# zxuno.net
KiCad netlist of a schematic drawn in EAGLE
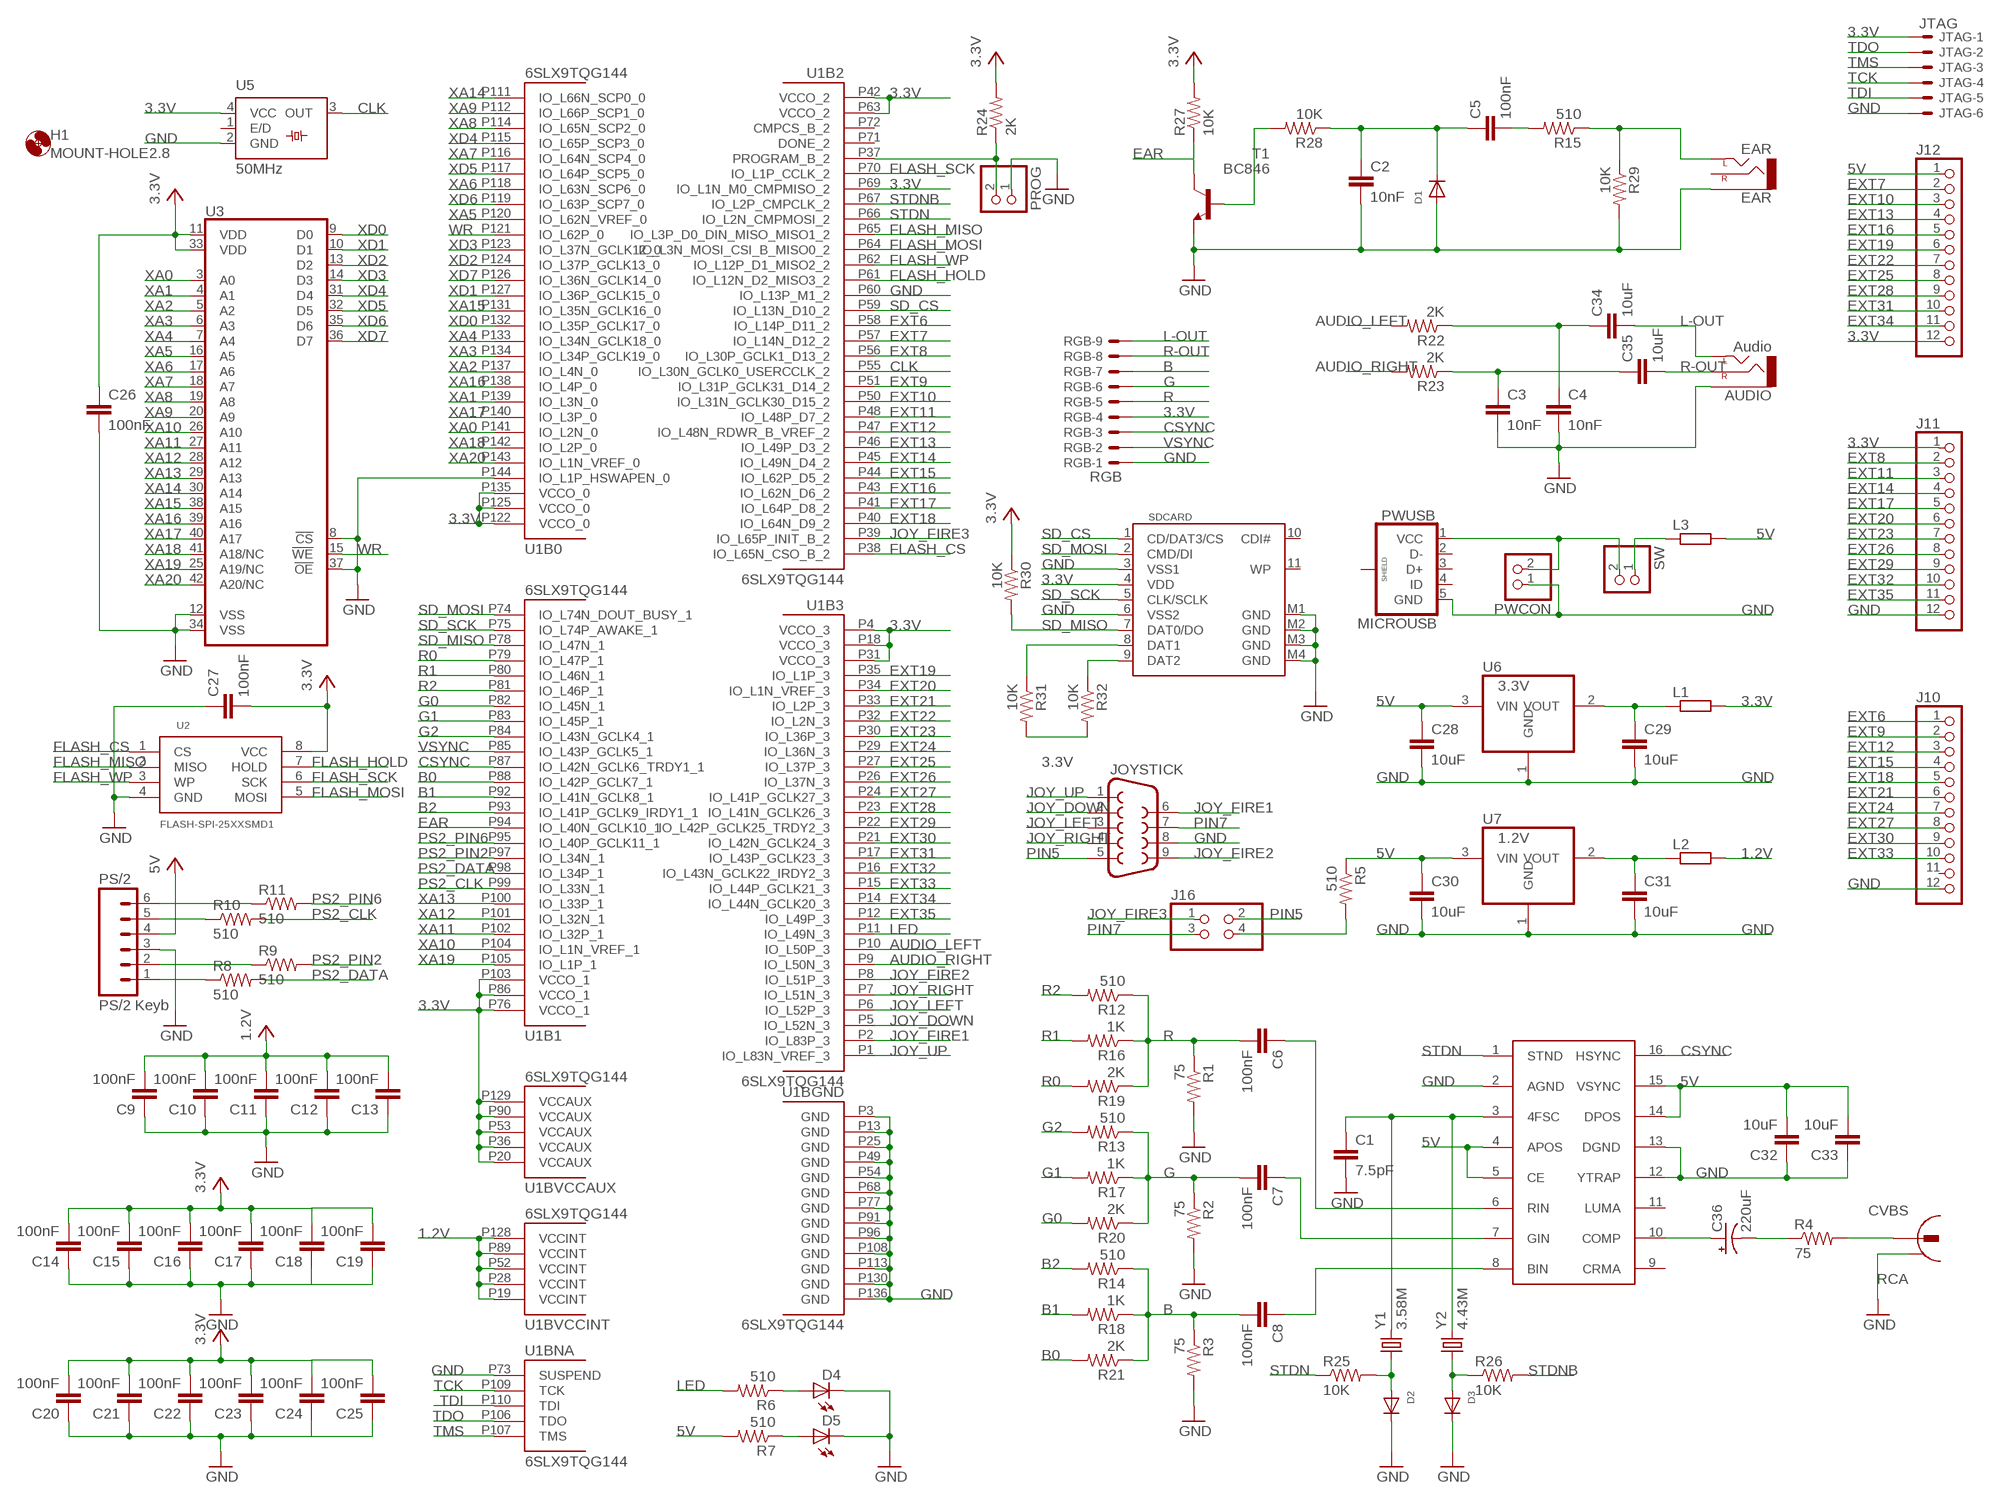
[diagram p0: schematic, sheet 1]

(export (version "E")
  (design (tool "Eeschema 10.0.6"))
  (components
    (comp (ref "AUDIO")
      (value "Audio")
      (footprint "eagle-import:AUDIO-JACK")
      (libsource (lib "eagle-import") (part "AUDIO-JACKPTH"))
    )
    (comp (ref "C1")
      (value "7.5pF")
      (footprint "eagle-import:C0805")
      (libsource (lib "eagle-import") (part "C-EUC0805"))
    )
    (comp (ref "C2")
      (value "10nF")
      (footprint "eagle-import:C0805")
      (libsource (lib "eagle-import") (part "C-EUC0805"))
    )
    (comp (ref "C3")
      (value "10nF")
      (footprint "eagle-import:C0805")
      (libsource (lib "eagle-import") (part "C-EUC0805"))
    )
    (comp (ref "C4")
      (value "10nF")
      (footprint "eagle-import:C0805")
      (libsource (lib "eagle-import") (part "C-EUC0805"))
    )
    (comp (ref "C5")
      (value "100nF")
      (footprint "eagle-import:C0603")
      (libsource (lib "eagle-import") (part "C-EUC0603"))
    )
    (comp (ref "C6")
      (value "100nF")
      (footprint "eagle-import:C0603")
      (libsource (lib "eagle-import") (part "C-EUC0603"))
    )
    (comp (ref "C7")
      (value "100nF")
      (footprint "eagle-import:C0603")
      (libsource (lib "eagle-import") (part "C-EUC0603"))
    )
    (comp (ref "C8")
      (value "100nF")
      (footprint "eagle-import:C0603")
      (libsource (lib "eagle-import") (part "C-EUC0603"))
    )
    (comp (ref "C9")
      (value "100nF")
      (footprint "eagle-import:C0603")
      (libsource (lib "eagle-import") (part "C-EUC0603"))
    )
    (comp (ref "C10")
      (value "100nF")
      (footprint "eagle-import:C0603")
      (libsource (lib "eagle-import") (part "C-EUC0603"))
    )
    (comp (ref "C11")
      (value "100nF")
      (footprint "eagle-import:C0603")
      (libsource (lib "eagle-import") (part "C-EUC0603"))
    )
    (comp (ref "C12")
      (value "100nF")
      (footprint "eagle-import:C0603")
      (libsource (lib "eagle-import") (part "C-EUC0603"))
    )
    (comp (ref "C13")
      (value "100nF")
      (footprint "eagle-import:C0603")
      (libsource (lib "eagle-import") (part "C-EUC0603"))
    )
    (comp (ref "C14")
      (value "100nF")
      (footprint "eagle-import:C0603")
      (libsource (lib "eagle-import") (part "C-EUC0603"))
    )
    (comp (ref "C15")
      (value "100nF")
      (footprint "eagle-import:C0603")
      (libsource (lib "eagle-import") (part "C-EUC0603"))
    )
    (comp (ref "C16")
      (value "100nF")
      (footprint "eagle-import:C0603")
      (libsource (lib "eagle-import") (part "C-EUC0603"))
    )
    (comp (ref "C17")
      (value "100nF")
      (footprint "eagle-import:C0603")
      (libsource (lib "eagle-import") (part "C-EUC0603"))
    )
    (comp (ref "C18")
      (value "100nF")
      (footprint "eagle-import:C0603")
      (libsource (lib "eagle-import") (part "C-EUC0603"))
    )
    (comp (ref "C19")
      (value "100nF")
      (footprint "eagle-import:C0603")
      (libsource (lib "eagle-import") (part "C-EUC0603"))
    )
    (comp (ref "C20")
      (value "100nF")
      (footprint "eagle-import:C0603")
      (libsource (lib "eagle-import") (part "C-EUC0603"))
    )
    (comp (ref "C21")
      (value "100nF")
      (footprint "eagle-import:C0603")
      (libsource (lib "eagle-import") (part "C-EUC0603"))
    )
    (comp (ref "C22")
      (value "100nF")
      (footprint "eagle-import:C0603")
      (libsource (lib "eagle-import") (part "C-EUC0603"))
    )
    (comp (ref "C23")
      (value "100nF")
      (footprint "eagle-import:C0603")
      (libsource (lib "eagle-import") (part "C-EUC0603"))
    )
    (comp (ref "C24")
      (value "100nF")
      (footprint "eagle-import:C0603")
      (libsource (lib "eagle-import") (part "C-EUC0603"))
    )
    (comp (ref "C25")
      (value "100nF")
      (footprint "eagle-import:C0603")
      (libsource (lib "eagle-import") (part "C-EUC0603"))
    )
    (comp (ref "C26")
      (value "100nF")
      (footprint "eagle-import:C0603")
      (libsource (lib "eagle-import") (part "C-EUC0603"))
    )
    (comp (ref "C27")
      (value "100nF")
      (footprint "eagle-import:C0603")
      (libsource (lib "eagle-import") (part "C-EUC0603"))
    )
    (comp (ref "C28")
      (value "10uF")
      (footprint "eagle-import:C0805")
      (libsource (lib "eagle-import") (part "C-EUC0805"))
    )
    (comp (ref "C29")
      (value "10uF")
      (footprint "eagle-import:C0805")
      (libsource (lib "eagle-import") (part "C-EUC0805"))
    )
    (comp (ref "C30")
      (value "10uF")
      (footprint "eagle-import:C0805")
      (libsource (lib "eagle-import") (part "C-EUC0805"))
    )
    (comp (ref "C31")
      (value "10uF")
      (footprint "eagle-import:C0805")
      (libsource (lib "eagle-import") (part "C-EUC0805"))
    )
    (comp (ref "C32")
      (value "10uF")
      (footprint "eagle-import:C0805")
      (libsource (lib "eagle-import") (part "C-EUC0805"))
    )
    (comp (ref "C33")
      (value "10uF")
      (footprint "eagle-import:C0805")
      (libsource (lib "eagle-import") (part "C-EUC0805"))
    )
    (comp (ref "C34")
      (value "10uF")
      (footprint "eagle-import:C0805")
      (libsource (lib "eagle-import") (part "C-EUC0805"))
    )
    (comp (ref "C35")
      (value "10uF")
      (footprint "eagle-import:C0805")
      (libsource (lib "eagle-import") (part "C-EUC0805"))
    )
    (comp (ref "C36")
      (value "220uF")
      (footprint "eagle-import:153CLV-0605")
      (libsource (lib "eagle-import") (part "CPOL-US153CLV-0605"))
    )
    (comp (ref "CVBS")
      (value "RCA")
      (footprint "eagle-import:RCA_JACK_RCJ-04X_-_DUPLICATE_1PRIMARY")
      (libsource (lib "eagle-import") (part "RCA_JACK_RCJ-04X_-_DUPLICATE_1"))
    )
    (comp (ref "D1")
      (value "DIODESOD-523")
      (footprint "eagle-import:SOD-523")
      (libsource (lib "eagle-import") (part "DIODESOD-523"))
    )
    (comp (ref "D2")
      (value "DIODESOD-523")
      (footprint "eagle-import:SOD-523")
      (libsource (lib "eagle-import") (part "DIODESOD-523"))
    )
    (comp (ref "D3")
      (value "DIODESOD-523")
      (footprint "eagle-import:SOD-523")
      (libsource (lib "eagle-import") (part "DIODESOD-523"))
    )
    (comp (ref "D4")
      (value "LEDCHIP-LED0805")
      (footprint "eagle-import:CHIP-LED0805")
      (libsource (lib "eagle-import") (part "LEDCHIP-LED0805"))
    )
    (comp (ref "D5")
      (value "LEDCHIP-LED0805")
      (footprint "eagle-import:CHIP-LED0805")
      (libsource (lib "eagle-import") (part "LEDCHIP-LED0805"))
    )
    (comp (ref "EAR")
      (value "EAR")
      (footprint "eagle-import:AUDIO-JACK")
      (libsource (lib "eagle-import") (part "AUDIO-JACKPTH"))
    )
    (comp (ref "H1")
      (value "MOUNT-HOLE2.8")
      (footprint "eagle-import:2,8")
      (libsource (lib "eagle-import") (part "MOUNT-HOLE2.8"))
    )
    (comp (ref "J10")
      (value "PINHD-1X12")
      (footprint "eagle-import:1X12")
      (libsource (lib "eagle-import") (part "PINHD-1X12"))
    )
    (comp (ref "J11")
      (value "PINHD-1X12")
      (footprint "eagle-import:1X12")
      (libsource (lib "eagle-import") (part "PINHD-1X12"))
    )
    (comp (ref "J12")
      (value "PINHD-1X12")
      (footprint "eagle-import:1X12")
      (libsource (lib "eagle-import") (part "PINHD-1X12"))
    )
    (comp (ref "J16")
      (value "PINHD-2X2")
      (footprint "eagle-import:2X02")
      (libsource (lib "eagle-import") (part "PINHD-2X2"))
    )
    (comp (ref "JOYSTICK")
      (value "DB9MALE")
      (footprint "eagle-import:DB9_MALE")
      (libsource (lib "eagle-import") (part "DB9MALE"))
    )
    (comp (ref "JTAG")
      (value "JTAG")
      (footprint "eagle-import:53047-06")
      (fields (field (name "MPN") "53047-0610-C"))
      (libsource (lib "eagle-import") (part "53?-06047"))
    )
    (comp (ref "L1")
      (value "R-EU_M0805")
      (footprint "eagle-import:M0805")
      (libsource (lib "eagle-import") (part "R-EU_M0805"))
    )
    (comp (ref "L2")
      (value "R-EU_M0805")
      (footprint "eagle-import:M0805")
      (libsource (lib "eagle-import") (part "R-EU_M0805"))
    )
    (comp (ref "L3")
      (value "R-EU_M0805")
      (footprint "eagle-import:M0805")
      (libsource (lib "eagle-import") (part "R-EU_M0805"))
    )
    (comp (ref "PROG")
      (value "PINHD-1X2")
      (footprint "eagle-import:1X02")
      (libsource (lib "eagle-import") (part "PINHD-1X2"))
    )
    (comp (ref "PS/2")
      (value "PS/2 Keyb")
      (footprint "eagle-import:DINC_MIN_TM_6_1PRIMARY")
      (libsource (lib "eagle-import") (part "DINC_MIN_TM_6_1"))
    )
    (comp (ref "PWCON")
      (value "PINHD-1X2")
      (footprint "eagle-import:1X02")
      (libsource (lib "eagle-import") (part "PINHD-1X2"))
    )
    (comp (ref "PWUSB")
      (value "MICROUSB")
      (footprint "eagle-import:MICRO_USB_1PRIMARY")
      (libsource (lib "eagle-import") (part "MICROUSB"))
    )
    (comp (ref "R1")
      (value "75")
      (footprint "eagle-import:M0805")
      (libsource (lib "eagle-import") (part "R-US_M0805"))
    )
    (comp (ref "R2")
      (value "75")
      (footprint "eagle-import:M0805")
      (libsource (lib "eagle-import") (part "R-US_M0805"))
    )
    (comp (ref "R3")
      (value "75")
      (footprint "eagle-import:M0805")
      (libsource (lib "eagle-import") (part "R-US_M0805"))
    )
    (comp (ref "R4")
      (value "75")
      (footprint "eagle-import:M0805")
      (libsource (lib "eagle-import") (part "R-US_M0805"))
    )
    (comp (ref "R5")
      (value "510")
      (footprint "eagle-import:M0805")
      (libsource (lib "eagle-import") (part "R-US_M0805"))
    )
    (comp (ref "R6")
      (value "510")
      (footprint "eagle-import:M0805")
      (libsource (lib "eagle-import") (part "R-US_M0805"))
    )
    (comp (ref "R7")
      (value "510")
      (footprint "eagle-import:M0805")
      (libsource (lib "eagle-import") (part "R-US_M0805"))
    )
    (comp (ref "R8")
      (value "510")
      (footprint "eagle-import:M0805")
      (libsource (lib "eagle-import") (part "R-US_M0805"))
    )
    (comp (ref "R9")
      (value "510")
      (footprint "eagle-import:M0805")
      (libsource (lib "eagle-import") (part "R-US_M0805"))
    )
    (comp (ref "R10")
      (value "510")
      (footprint "eagle-import:M0805")
      (libsource (lib "eagle-import") (part "R-US_M0805"))
    )
    (comp (ref "R11")
      (value "510")
      (footprint "eagle-import:M0805")
      (libsource (lib "eagle-import") (part "R-US_M0805"))
    )
    (comp (ref "R12")
      (value "510")
      (footprint "eagle-import:M0805")
      (libsource (lib "eagle-import") (part "R-US_M0805"))
    )
    (comp (ref "R13")
      (value "510")
      (footprint "eagle-import:M0805")
      (libsource (lib "eagle-import") (part "R-US_M0805"))
    )
    (comp (ref "R14")
      (value "510")
      (footprint "eagle-import:M0805")
      (libsource (lib "eagle-import") (part "R-US_M0805"))
    )
    (comp (ref "R15")
      (value "510")
      (footprint "eagle-import:M0805")
      (libsource (lib "eagle-import") (part "R-US_M0805"))
    )
    (comp (ref "R16")
      (value "1K")
      (footprint "eagle-import:M0805")
      (libsource (lib "eagle-import") (part "R-US_M0805"))
    )
    (comp (ref "R17")
      (value "1K")
      (footprint "eagle-import:M0805")
      (libsource (lib "eagle-import") (part "R-US_M0805"))
    )
    (comp (ref "R18")
      (value "1K")
      (footprint "eagle-import:M0805")
      (libsource (lib "eagle-import") (part "R-US_M0805"))
    )
    (comp (ref "R19")
      (value "2K")
      (footprint "eagle-import:M0805")
      (libsource (lib "eagle-import") (part "R-US_M0805"))
    )
    (comp (ref "R20")
      (value "2K")
      (footprint "eagle-import:M0805")
      (libsource (lib "eagle-import") (part "R-US_M0805"))
    )
    (comp (ref "R21")
      (value "2K")
      (footprint "eagle-import:M0805")
      (libsource (lib "eagle-import") (part "R-US_M0805"))
    )
    (comp (ref "R22")
      (value "2K")
      (footprint "eagle-import:M0805")
      (libsource (lib "eagle-import") (part "R-US_M0805"))
    )
    (comp (ref "R23")
      (value "2K")
      (footprint "eagle-import:M0805")
      (libsource (lib "eagle-import") (part "R-US_M0805"))
    )
    (comp (ref "R24")
      (value "2K")
      (footprint "eagle-import:M0805")
      (libsource (lib "eagle-import") (part "R-US_M0805"))
    )
    (comp (ref "R25")
      (value "10K")
      (footprint "eagle-import:M0805")
      (libsource (lib "eagle-import") (part "R-US_M0805"))
    )
    (comp (ref "R26")
      (value "10K")
      (footprint "eagle-import:M0805")
      (libsource (lib "eagle-import") (part "R-US_M0805"))
    )
    (comp (ref "R27")
      (value "10K")
      (footprint "eagle-import:M0805")
      (libsource (lib "eagle-import") (part "R-US_M0805"))
    )
    (comp (ref "R28")
      (value "10K")
      (footprint "eagle-import:M0805")
      (libsource (lib "eagle-import") (part "R-US_M0805"))
    )
    (comp (ref "R29")
      (value "10K")
      (footprint "eagle-import:M0805")
      (libsource (lib "eagle-import") (part "R-US_M0805"))
    )
    (comp (ref "R30")
      (value "10K")
      (footprint "eagle-import:M0805")
      (libsource (lib "eagle-import") (part "R-US_M0805"))
    )
    (comp (ref "R31")
      (value "10K")
      (footprint "eagle-import:M0805")
      (libsource (lib "eagle-import") (part "R-US_M0805"))
    )
    (comp (ref "R32")
      (value "10K")
      (footprint "eagle-import:M0805")
      (libsource (lib "eagle-import") (part "R-US_M0805"))
    )
    (comp (ref "RGB")
      (value "RGB")
      (footprint "eagle-import:53048-09")
      (fields (field (name "MPN") "53048-0910"))
      (libsource (lib "eagle-import") (part "53?-09048"))
    )
    (comp (ref "SDCARD")
      (value "SDCARD")
      (footprint "eagle-import:SDCMF-10915W010")
      (libsource (lib "eagle-import") (part "SDCARD"))
    )
    (comp (ref "SW")
      (value "PINHD-1X2")
      (footprint "eagle-import:1X02")
      (libsource (lib "eagle-import") (part "PINHD-1X2"))
    )
    (comp (ref "T1")
      (value "BC846")
      (footprint "eagle-import:SOT23")
      (libsource (lib "eagle-import") (part "BC846"))
    )
    (comp (ref "U1")
      (value "6SLX9TQG144")
      (footprint "eagle-import:TQ144")
      (libsource (lib "eagle-import") (part "6SLX9TQG144"))
    )
    (comp (ref "U2")
      (value "FLASH-SPI-25XXSMD1")
      (footprint "eagle-import:SO08-EIAJ")
      (libsource (lib "eagle-import") (part "FLASH-SPI-25XXSMD1"))
    )
    (comp (ref "U3")
      (value "ISSI_SRAM_8BIT")
      (footprint "eagle-import:TSOP44-II")
      (libsource (lib "eagle-import") (part "ISSI_SRAM_8BIT"))
    )
    (comp (ref "U4")
      (value "AD724")
      (footprint "eagle-import:SO16W")
      (libsource (lib "eagle-import") (part "AD725"))
    )
    (comp (ref "U5")
      (value "50MHz")
      (footprint "eagle-import:SM_OSC_1PRIMARY")
      (libsource (lib "eagle-import") (part "SM_OSC_1"))
    )
    (comp (ref "U6")
      (value "3.3V")
      (footprint "eagle-import:SOT223")
      (fields (field (name "MPN") "REG1117"))
      (libsource (lib "eagle-import") (part "REG1117"))
    )
    (comp (ref "U7")
      (value "1.2V")
      (footprint "eagle-import:SOT223")
      (fields (field (name "MPN") "REG1117"))
      (libsource (lib "eagle-import") (part "REG1117"))
    )
    (comp (ref "Y1")
      (value "3.58M")
      (footprint "eagle-import:HC49UP")
      (libsource (lib "eagle-import") (part "CRYSTALHC49UP"))
    )
    (comp (ref "Y2")
      (value "4.43M")
      (footprint "eagle-import:HC49UP")
      (libsource (lib "eagle-import") (part "CRYSTALHC49UP"))
    )
  )
  (nets
    (net (code "1") (name "/AUDIO_LEFT") (class "Default")
      (node (ref "R22") (pin "2") (pinfunction "2_2") (pintype "passive"))
      (node (ref "U1") (pin "P10") (pinfunction "IO_L50P_3_P10") (pintype "bidirectional"))
    )
    (net (code "2") (name "/AUDIO_RIGHT") (class "Default")
      (node (ref "R23") (pin "2") (pinfunction "2_2") (pintype "passive"))
      (node (ref "U1") (pin "P9") (pinfunction "IO_L50N_3_P9") (pintype "bidirectional"))
    )
    (net (code "3") (name "/B") (class "Default")
      (node (ref "C8") (pin "2") (pinfunction "2_2") (pintype "passive"))
      (node (ref "R14") (pin "1") (pinfunction "1_1") (pintype "passive"))
      (node (ref "R18") (pin "1") (pinfunction "1_1") (pintype "passive"))
      (node (ref "R21") (pin "1") (pinfunction "1_1") (pintype "passive"))
      (node (ref "R3") (pin "1") (pinfunction "1_1") (pintype "passive"))
      (node (ref "RGB") (pin "7") (pinfunction "S_7") (pintype "passive"))
    )
    (net (code "4") (name "/B0") (class "Default")
      (node (ref "R21") (pin "2") (pinfunction "2_2") (pintype "passive"))
      (node (ref "U1") (pin "P88") (pinfunction "IO_L42P_GCLK7_1_P88") (pintype "bidirectional"))
    )
    (net (code "5") (name "/B1") (class "Default")
      (node (ref "R18") (pin "2") (pinfunction "2_2") (pintype "passive"))
      (node (ref "U1") (pin "P92") (pinfunction "IO_L41N_GCLK8_1_P92") (pintype "bidirectional"))
    )
    (net (code "6") (name "/B2") (class "Default")
      (node (ref "R14") (pin "2") (pinfunction "2_2") (pintype "passive"))
      (node (ref "U1") (pin "P93") (pinfunction "IO_L41P_GCLK9_IRDY1_1_P93") (pintype "bidirectional"))
    )
    (net (code "7") (name "/CLK") (class "Default")
      (node (ref "U1") (pin "P55") (pinfunction "IO_L30N_GCLK0_USERCCLK_2_P55") (pintype "bidirectional"))
      (node (ref "U5") (pin "3") (pinfunction "OUT_3") (pintype "output"))
    )
    (net (code "8") (name "/CSYNC") (class "Default")
      (node (ref "RGB") (pin "3") (pinfunction "S_3") (pintype "passive"))
      (node (ref "U1") (pin "P87") (pinfunction "IO_L42N_GCLK6_TRDY1_1_P87") (pintype "bidirectional"))
      (node (ref "U4") (pin "16") (pinfunction "HSYNC_16") (pintype "bidirectional"))
    )
    (net (code "9") (name "/EAR") (class "Default")
      (node (ref "R27") (pin "1") (pinfunction "1_1") (pintype "passive"))
      (node (ref "T1") (pin "3") (pinfunction "C_3") (pintype "passive"))
      (node (ref "U1") (pin "P94") (pinfunction "IO_L40N_GCLK10_1_P94") (pintype "bidirectional"))
    )
    (net (code "10") (name "/EXT6") (class "Default")
      (node (ref "J10") (pin "1") (pinfunction "1_1") (pintype "passive"))
      (node (ref "U1") (pin "P58") (pinfunction "IO_L14P_D11_2_P58") (pintype "bidirectional"))
    )
    (net (code "11") (name "/EXT7") (class "Default")
      (node (ref "J12") (pin "2") (pinfunction "2_2") (pintype "passive"))
      (node (ref "U1") (pin "P57") (pinfunction "IO_L14N_D12_2_P57") (pintype "bidirectional"))
    )
    (net (code "12") (name "/EXT8") (class "Default")
      (node (ref "J11") (pin "2") (pinfunction "2_2") (pintype "passive"))
      (node (ref "U1") (pin "P56") (pinfunction "IO_L30P_GCLK1_D13_2_P56") (pintype "bidirectional"))
    )
    (net (code "13") (name "/EXT9") (class "Default")
      (node (ref "J10") (pin "2") (pinfunction "2_2") (pintype "passive"))
      (node (ref "U1") (pin "P51") (pinfunction "IO_L31P_GCLK31_D14_2_P51") (pintype "bidirectional"))
    )
    (net (code "14") (name "/EXT10") (class "Default")
      (node (ref "J12") (pin "3") (pinfunction "3_3") (pintype "passive"))
      (node (ref "U1") (pin "P50") (pinfunction "IO_L31N_GCLK30_D15_2_P50") (pintype "bidirectional"))
    )
    (net (code "15") (name "/EXT11") (class "Default")
      (node (ref "J11") (pin "3") (pinfunction "3_3") (pintype "passive"))
      (node (ref "U1") (pin "P48") (pinfunction "IO_L48P_D7_2_P48") (pintype "bidirectional"))
    )
    (net (code "16") (name "/EXT12") (class "Default")
      (node (ref "J10") (pin "3") (pinfunction "3_3") (pintype "passive"))
      (node (ref "U1") (pin "P47") (pinfunction "IO_L48N_RDWR_B_VREF_2_P47") (pintype "bidirectional"))
    )
    (net (code "17") (name "/EXT13") (class "Default")
      (node (ref "J12") (pin "4") (pinfunction "4_4") (pintype "passive"))
      (node (ref "U1") (pin "P46") (pinfunction "IO_L49P_D3_2_P46") (pintype "bidirectional"))
    )
    (net (code "18") (name "/EXT14") (class "Default")
      (node (ref "J11") (pin "4") (pinfunction "4_4") (pintype "passive"))
      (node (ref "U1") (pin "P45") (pinfunction "IO_L49N_D4_2_P45") (pintype "bidirectional"))
    )
    (net (code "19") (name "/EXT15") (class "Default")
      (node (ref "J10") (pin "4") (pinfunction "4_4") (pintype "passive"))
      (node (ref "U1") (pin "P44") (pinfunction "IO_L62P_D5_2_P44") (pintype "bidirectional"))
    )
    (net (code "20") (name "/EXT16") (class "Default")
      (node (ref "J12") (pin "5") (pinfunction "5_5") (pintype "passive"))
      (node (ref "U1") (pin "P43") (pinfunction "IO_L62N_D6_2_P43") (pintype "bidirectional"))
    )
    (net (code "21") (name "/EXT17") (class "Default")
      (node (ref "J11") (pin "5") (pinfunction "5_5") (pintype "passive"))
      (node (ref "U1") (pin "P41") (pinfunction "IO_L64P_D8_2_P41") (pintype "bidirectional"))
    )
    (net (code "22") (name "/EXT18") (class "Default")
      (node (ref "J10") (pin "5") (pinfunction "5_5") (pintype "passive"))
      (node (ref "U1") (pin "P40") (pinfunction "IO_L64N_D9_2_P40") (pintype "bidirectional"))
    )
    (net (code "23") (name "/EXT19") (class "Default")
      (node (ref "J12") (pin "6") (pinfunction "6_6") (pintype "passive"))
      (node (ref "U1") (pin "P35") (pinfunction "IO_L1P_3_P35") (pintype "bidirectional"))
    )
    (net (code "24") (name "/EXT20") (class "Default")
      (node (ref "J11") (pin "6") (pinfunction "6_6") (pintype "passive"))
      (node (ref "U1") (pin "P34") (pinfunction "IO_L1N_VREF_3_P34") (pintype "bidirectional"))
    )
    (net (code "25") (name "/EXT21") (class "Default")
      (node (ref "J10") (pin "6") (pinfunction "6_6") (pintype "passive"))
      (node (ref "U1") (pin "P33") (pinfunction "IO_L2P_3_P33") (pintype "bidirectional"))
    )
    (net (code "26") (name "/EXT22") (class "Default")
      (node (ref "J12") (pin "7") (pinfunction "7_7") (pintype "passive"))
      (node (ref "U1") (pin "P32") (pinfunction "IO_L2N_3_P32") (pintype "bidirectional"))
    )
    (net (code "27") (name "/EXT23") (class "Default")
      (node (ref "J11") (pin "7") (pinfunction "7_7") (pintype "passive"))
      (node (ref "U1") (pin "P30") (pinfunction "IO_L36P_3_P30") (pintype "bidirectional"))
    )
    (net (code "28") (name "/EXT24") (class "Default")
      (node (ref "J10") (pin "7") (pinfunction "7_7") (pintype "passive"))
      (node (ref "U1") (pin "P29") (pinfunction "IO_L36N_3_P29") (pintype "bidirectional"))
    )
    (net (code "29") (name "/EXT25") (class "Default")
      (node (ref "J12") (pin "8") (pinfunction "8_8") (pintype "passive"))
      (node (ref "U1") (pin "P27") (pinfunction "IO_L37P_3_P27") (pintype "bidirectional"))
    )
    (net (code "30") (name "/EXT26") (class "Default")
      (node (ref "J11") (pin "8") (pinfunction "8_8") (pintype "passive"))
      (node (ref "U1") (pin "P26") (pinfunction "IO_L37N_3_P26") (pintype "bidirectional"))
    )
    (net (code "31") (name "/EXT27") (class "Default")
      (node (ref "J10") (pin "8") (pinfunction "8_8") (pintype "passive"))
      (node (ref "U1") (pin "P24") (pinfunction "IO_L41P_GCLK27_3_P24") (pintype "bidirectional"))
    )
    (net (code "32") (name "/EXT28") (class "Default")
      (node (ref "J12") (pin "9") (pinfunction "9_9") (pintype "passive"))
      (node (ref "U1") (pin "P23") (pinfunction "IO_L41N_GCLK26_3_P23") (pintype "bidirectional"))
    )
    (net (code "33") (name "/EXT29") (class "Default")
      (node (ref "J11") (pin "9") (pinfunction "9_9") (pintype "passive"))
      (node (ref "U1") (pin "P22") (pinfunction "IO_L42P_GCLK25_TRDY2_3_P22") (pintype "bidirectional"))
    )
    (net (code "34") (name "/EXT30") (class "Default")
      (node (ref "J10") (pin "9") (pinfunction "9_9") (pintype "passive"))
      (node (ref "U1") (pin "P21") (pinfunction "IO_L42N_GCLK24_3_P21") (pintype "bidirectional"))
    )
    (net (code "35") (name "/EXT31") (class "Default")
      (node (ref "J12") (pin "10") (pinfunction "10_10") (pintype "passive"))
      (node (ref "U1") (pin "P17") (pinfunction "IO_L43P_GCLK23_3_P17") (pintype "bidirectional"))
    )
    (net (code "36") (name "/EXT32") (class "Default")
      (node (ref "J11") (pin "10") (pinfunction "10_10") (pintype "passive"))
      (node (ref "U1") (pin "P16") (pinfunction "IO_L43N_GCLK22_IRDY2_3_P16") (pintype "bidirectional"))
    )
    (net (code "37") (name "/EXT33") (class "Default")
      (node (ref "J10") (pin "10") (pinfunction "10_10") (pintype "passive"))
      (node (ref "U1") (pin "P15") (pinfunction "IO_L44P_GCLK21_3_P15") (pintype "bidirectional"))
    )
    (net (code "38") (name "/EXT34") (class "Default")
      (node (ref "J12") (pin "11") (pinfunction "11_11") (pintype "passive"))
      (node (ref "U1") (pin "P14") (pinfunction "IO_L44N_GCLK20_3_P14") (pintype "bidirectional"))
    )
    (net (code "39") (name "/EXT35") (class "Default")
      (node (ref "J11") (pin "11") (pinfunction "11_11") (pintype "passive"))
      (node (ref "U1") (pin "P12") (pinfunction "IO_L49P_3_P12") (pintype "bidirectional"))
    )
    (net (code "40") (name "/FLASH_CS") (class "Default")
      (node (ref "U1") (pin "P38") (pinfunction "IO_L65N_CSO_B_2_P38") (pintype "bidirectional"))
      (node (ref "U2") (pin "1") (pinfunction "CS_1") (pintype "bidirectional"))
    )
    (net (code "41") (name "/FLASH_HOLD") (class "Default")
      (node (ref "U1") (pin "P61") (pinfunction "IO_L12N_D2_MISO3_2_P61") (pintype "bidirectional"))
      (node (ref "U2") (pin "7") (pinfunction "HOLD_7") (pintype "bidirectional"))
    )
    (net (code "42") (name "/FLASH_MISO") (class "Default")
      (node (ref "U1") (pin "P65") (pinfunction "IO_L3P_D0_DIN_MISO_MISO1_2_P65") (pintype "bidirectional"))
      (node (ref "U2") (pin "2") (pinfunction "MISO_2") (pintype "bidirectional"))
    )
    (net (code "43") (name "/FLASH_MOSI") (class "Default")
      (node (ref "U1") (pin "P64") (pinfunction "IO_L3N_MOSI_CSI_B_MISO0_2_P64") (pintype "bidirectional"))
      (node (ref "U2") (pin "5") (pinfunction "MOSI_5") (pintype "bidirectional"))
    )
    (net (code "44") (name "/FLASH_SCK") (class "Default")
      (node (ref "U1") (pin "P70") (pinfunction "IO_L1P_CCLK_2_P70") (pintype "bidirectional"))
      (node (ref "U2") (pin "6") (pinfunction "SCK_6") (pintype "bidirectional"))
    )
    (net (code "45") (name "/FLASH_WP") (class "Default")
      (node (ref "U1") (pin "P62") (pinfunction "IO_L12P_D1_MISO2_2_P62") (pintype "bidirectional"))
      (node (ref "U2") (pin "3") (pinfunction "WP_3") (pintype "bidirectional"))
    )
    (net (code "46") (name "/G") (class "Default")
      (node (ref "C7") (pin "2") (pinfunction "2_2") (pintype "passive"))
      (node (ref "R13") (pin "1") (pinfunction "1_1") (pintype "passive"))
      (node (ref "R17") (pin "1") (pinfunction "1_1") (pintype "passive"))
      (node (ref "R2") (pin "1") (pinfunction "1_1") (pintype "passive"))
      (node (ref "R20") (pin "1") (pinfunction "1_1") (pintype "passive"))
      (node (ref "RGB") (pin "6") (pinfunction "S_6") (pintype "passive"))
    )
    (net (code "47") (name "/G0") (class "Default")
      (node (ref "R20") (pin "2") (pinfunction "2_2") (pintype "passive"))
      (node (ref "U1") (pin "P82") (pinfunction "IO_L45N_1_P82") (pintype "bidirectional"))
    )
    (net (code "48") (name "/G1") (class "Default")
      (node (ref "R17") (pin "2") (pinfunction "2_2") (pintype "passive"))
      (node (ref "U1") (pin "P83") (pinfunction "IO_L45P_1_P83") (pintype "bidirectional"))
    )
    (net (code "49") (name "/G2") (class "Default")
      (node (ref "R13") (pin "2") (pinfunction "2_2") (pintype "passive"))
      (node (ref "U1") (pin "P84") (pinfunction "IO_L43N_GCLK4_1_P84") (pintype "bidirectional"))
    )
    (net (code "50") (name "/JOY_DOWN") (class "Default")
      (node (ref "JOYSTICK") (pin "2") (pinfunction "2_2") (pintype "passive"))
      (node (ref "U1") (pin "P5") (pinfunction "IO_L52N_3_P5") (pintype "bidirectional"))
    )
    (net (code "51") (name "/JOY_FIRE1") (class "Default")
      (node (ref "JOYSTICK") (pin "6") (pinfunction "6_6") (pintype "passive"))
      (node (ref "U1") (pin "P2") (pinfunction "IO_L83P_3_P2") (pintype "bidirectional"))
    )
    (net (code "52") (name "/JOY_FIRE2") (class "Default")
      (node (ref "JOYSTICK") (pin "9") (pinfunction "9_9") (pintype "passive"))
      (node (ref "U1") (pin "P8") (pinfunction "IO_L51P_3_P8") (pintype "bidirectional"))
    )
    (net (code "53") (name "/JOY_FIRE3") (class "Default")
      (node (ref "J16") (pin "1") (pinfunction "1_1") (pintype "passive"))
      (node (ref "U1") (pin "P39") (pinfunction "IO_L65P_INIT_B_2_P39") (pintype "bidirectional"))
    )
    (net (code "54") (name "/JOY_LEFT") (class "Default")
      (node (ref "JOYSTICK") (pin "3") (pinfunction "3_3") (pintype "passive"))
      (node (ref "U1") (pin "P6") (pinfunction "IO_L52P_3_P6") (pintype "bidirectional"))
    )
    (net (code "55") (name "/JOY_RIGHT") (class "Default")
      (node (ref "JOYSTICK") (pin "4") (pinfunction "4_4") (pintype "passive"))
      (node (ref "U1") (pin "P7") (pinfunction "IO_L51N_3_P7") (pintype "bidirectional"))
    )
    (net (code "56") (name "/JOY_UP") (class "Default")
      (node (ref "JOYSTICK") (pin "1") (pinfunction "1_1") (pintype "passive"))
      (node (ref "U1") (pin "P1") (pinfunction "IO_L83N_VREF_3_P1") (pintype "bidirectional"))
    )
    (net (code "57") (name "/L-OUT") (class "Default")
      (node (ref "AUDIO") (pin "TIP") (pinfunction "LEFT_TIP") (pintype "bidirectional"))
      (node (ref "C34") (pin "2") (pinfunction "2_2") (pintype "passive"))
      (node (ref "RGB") (pin "9") (pinfunction "S_9") (pintype "passive"))
    )
    (net (code "58") (name "/LED") (class "Default")
      (node (ref "R6") (pin "2") (pinfunction "2_2") (pintype "passive"))
      (node (ref "U1") (pin "P11") (pinfunction "IO_L49N_3_P11") (pintype "bidirectional"))
    )
    (net (code "59") (name "/PIN5") (class "Default")
      (node (ref "J16") (pin "2") (pinfunction "2_2") (pintype "passive"))
      (node (ref "JOYSTICK") (pin "5") (pinfunction "5_5") (pintype "passive"))
    )
    (net (code "60") (name "/PIN7") (class "Default")
      (node (ref "J16") (pin "3") (pinfunction "3_3") (pintype "passive"))
      (node (ref "JOYSTICK") (pin "7") (pinfunction "7_7") (pintype "passive"))
    )
    (net (code "61") (name "/PS2_CLK") (class "Default")
      (node (ref "R10") (pin "2") (pinfunction "2_2") (pintype "passive"))
      (node (ref "U1") (pin "P99") (pinfunction "IO_L33N_1_P99") (pintype "bidirectional"))
    )
    (net (code "62") (name "/PS2_DATA") (class "Default")
      (node (ref "R8") (pin "2") (pinfunction "2_2") (pintype "passive"))
      (node (ref "U1") (pin "P98") (pinfunction "IO_L34P_1_P98") (pintype "bidirectional"))
    )
    (net (code "63") (name "/PS2_PIN2") (class "Default")
      (node (ref "R9") (pin "2") (pinfunction "2_2") (pintype "passive"))
      (node (ref "U1") (pin "P97") (pinfunction "IO_L34N_1_P97") (pintype "bidirectional"))
    )
    (net (code "64") (name "/PS2_PIN6") (class "Default")
      (node (ref "R11") (pin "2") (pinfunction "2_2") (pintype "passive"))
      (node (ref "U1") (pin "P95") (pinfunction "IO_L40P_GCLK11_1_P95") (pintype "bidirectional"))
    )
    (net (code "65") (name "/R") (class "Default")
      (node (ref "C6") (pin "2") (pinfunction "2_2") (pintype "passive"))
      (node (ref "R1") (pin "1") (pinfunction "1_1") (pintype "passive"))
      (node (ref "R12") (pin "1") (pinfunction "1_1") (pintype "passive"))
      (node (ref "R16") (pin "1") (pinfunction "1_1") (pintype "passive"))
      (node (ref "R19") (pin "1") (pinfunction "1_1") (pintype "passive"))
      (node (ref "RGB") (pin "5") (pinfunction "S_5") (pintype "passive"))
    )
    (net (code "66") (name "/R-OUT") (class "Default")
      (node (ref "AUDIO") (pin "RING") (pinfunction "RIGHT_RING") (pintype "bidirectional"))
      (node (ref "C35") (pin "2") (pinfunction "2_2") (pintype "passive"))
      (node (ref "RGB") (pin "8") (pinfunction "S_8") (pintype "passive"))
    )
    (net (code "67") (name "/R0") (class "Default")
      (node (ref "R19") (pin "2") (pinfunction "2_2") (pintype "passive"))
      (node (ref "U1") (pin "P79") (pinfunction "IO_L47P_1_P79") (pintype "bidirectional"))
    )
    (net (code "68") (name "/R1") (class "Default")
      (node (ref "R16") (pin "2") (pinfunction "2_2") (pintype "passive"))
      (node (ref "U1") (pin "P80") (pinfunction "IO_L46N_1_P80") (pintype "bidirectional"))
    )
    (net (code "69") (name "/R2") (class "Default")
      (node (ref "R12") (pin "2") (pinfunction "2_2") (pintype "passive"))
      (node (ref "U1") (pin "P81") (pinfunction "IO_L46P_1_P81") (pintype "bidirectional"))
    )
    (net (code "70") (name "/SD_CS") (class "Default")
      (node (ref "SDCARD") (pin "1") (pinfunction "CD/DAT3/CS_1") (pintype "bidirectional"))
      (node (ref "U1") (pin "P59") (pinfunction "IO_L13N_D10_2_P59") (pintype "bidirectional"))
    )
    (net (code "71") (name "/SD_MISO") (class "Default")
      (node (ref "R30") (pin "2") (pinfunction "2_2") (pintype "passive"))
      (node (ref "SDCARD") (pin "7") (pinfunction "DAT0/DO_7") (pintype "bidirectional"))
      (node (ref "U1") (pin "P78") (pinfunction "IO_L47N_1_P78") (pintype "bidirectional"))
    )
    (net (code "72") (name "/SD_MOSI") (class "Default")
      (node (ref "SDCARD") (pin "2") (pinfunction "CMD/DI_2") (pintype "bidirectional"))
      (node (ref "U1") (pin "P74") (pinfunction "IO_L74N_DOUT_BUSY_1_P74") (pintype "bidirectional"))
    )
    (net (code "73") (name "/SD_SCK") (class "Default")
      (node (ref "SDCARD") (pin "5") (pinfunction "CLK/SCLK_5") (pintype "bidirectional"))
      (node (ref "U1") (pin "P75") (pinfunction "IO_L74P_AWAKE_1_P75") (pintype "bidirectional"))
    )
    (net (code "74") (name "/STDN") (class "Default")
      (node (ref "R25") (pin "1") (pinfunction "1_1") (pintype "passive"))
      (node (ref "U1") (pin "P66") (pinfunction "IO_L2N_CMPMOSI_2_P66") (pintype "bidirectional"))
      (node (ref "U4") (pin "1") (pinfunction "STND_1") (pintype "bidirectional"))
    )
    (net (code "75") (name "/STDNB") (class "Default")
      (node (ref "R26") (pin "2") (pinfunction "2_2") (pintype "passive"))
      (node (ref "U1") (pin "P67") (pinfunction "IO_L2P_CMPCLK_2_P67") (pintype "bidirectional"))
    )
    (net (code "76") (name "/TCK") (class "Default")
      (node (ref "JTAG") (pin "4") (pinfunction "S_4") (pintype "passive"))
      (node (ref "U1") (pin "P109") (pinfunction "TCK_P109") (pintype "input"))
    )
    (net (code "77") (name "/TDI") (class "Default")
      (node (ref "JTAG") (pin "5") (pinfunction "S_5") (pintype "passive"))
      (node (ref "U1") (pin "P110") (pinfunction "TDI_P110") (pintype "input"))
    )
    (net (code "78") (name "/TDO") (class "Default")
      (node (ref "JTAG") (pin "2") (pinfunction "S_2") (pintype "passive"))
      (node (ref "U1") (pin "P106") (pinfunction "TDO_P106") (pintype "output"))
    )
    (net (code "79") (name "/TMS") (class "Default")
      (node (ref "JTAG") (pin "3") (pinfunction "S_3") (pintype "passive"))
      (node (ref "U1") (pin "P107") (pinfunction "TMS_P107") (pintype "input"))
    )
    (net (code "80") (name "/VSYNC") (class "Default")
      (node (ref "RGB") (pin "2") (pinfunction "S_2") (pintype "passive"))
      (node (ref "U1") (pin "P85") (pinfunction "IO_L43P_GCLK5_1_P85") (pintype "bidirectional"))
    )
    (net (code "81") (name "/WR") (class "Default")
      (node (ref "U1") (pin "P121") (pinfunction "IO_L62P_0_P121") (pintype "bidirectional"))
      (node (ref "U3") (pin "15") (pinfunction "~{WE}_15") (pintype "input"))
    )
    (net (code "82") (name "/XA0") (class "Default")
      (node (ref "U1") (pin "P141") (pinfunction "IO_L2N_0_P141") (pintype "bidirectional"))
      (node (ref "U3") (pin "3") (pinfunction "A0_3") (pintype "input"))
    )
    (net (code "83") (name "/XA1") (class "Default")
      (node (ref "U1") (pin "P139") (pinfunction "IO_L3N_0_P139") (pintype "bidirectional"))
      (node (ref "U3") (pin "4") (pinfunction "A1_4") (pintype "input"))
    )
    (net (code "84") (name "/XA2") (class "Default")
      (node (ref "U1") (pin "P137") (pinfunction "IO_L4N_0_P137") (pintype "bidirectional"))
      (node (ref "U3") (pin "5") (pinfunction "A2_5") (pintype "input"))
    )
    (net (code "85") (name "/XA3") (class "Default")
      (node (ref "U1") (pin "P134") (pinfunction "IO_L34P_GCLK19_0_P134") (pintype "bidirectional"))
      (node (ref "U3") (pin "6") (pinfunction "A3_6") (pintype "input"))
    )
    (net (code "86") (name "/XA4") (class "Default")
      (node (ref "U1") (pin "P133") (pinfunction "IO_L34N_GCLK18_0_P133") (pintype "bidirectional"))
      (node (ref "U3") (pin "7") (pinfunction "A4_7") (pintype "input"))
    )
    (net (code "87") (name "/XA5") (class "Default")
      (node (ref "U1") (pin "P120") (pinfunction "IO_L62N_VREF_0_P120") (pintype "bidirectional"))
      (node (ref "U3") (pin "16") (pinfunction "A5_16") (pintype "input"))
    )
    (net (code "88") (name "/XA6") (class "Default")
      (node (ref "U1") (pin "P118") (pinfunction "IO_L63N_SCP6_0_P118") (pintype "bidirectional"))
      (node (ref "U3") (pin "17") (pinfunction "A6_17") (pintype "input"))
    )
    (net (code "89") (name "/XA7") (class "Default")
      (node (ref "U1") (pin "P116") (pinfunction "IO_L64N_SCP4_0_P116") (pintype "bidirectional"))
      (node (ref "U3") (pin "18") (pinfunction "A7_18") (pintype "input"))
    )
    (net (code "90") (name "/XA8") (class "Default")
      (node (ref "U1") (pin "P114") (pinfunction "IO_L65N_SCP2_0_P114") (pintype "bidirectional"))
      (node (ref "U3") (pin "19") (pinfunction "A8_19") (pintype "input"))
    )
    (net (code "91") (name "/XA9") (class "Default")
      (node (ref "U1") (pin "P112") (pinfunction "IO_L66P_SCP1_0_P112") (pintype "bidirectional"))
      (node (ref "U3") (pin "20") (pinfunction "A9_20") (pintype "input"))
    )
    (net (code "92") (name "/XA10") (class "Default")
      (node (ref "U1") (pin "P104") (pinfunction "IO_L1N_VREF_1_P104") (pintype "bidirectional"))
      (node (ref "U3") (pin "26") (pinfunction "A10_26") (pintype "input"))
    )
    (net (code "93") (name "/XA11") (class "Default")
      (node (ref "U1") (pin "P102") (pinfunction "IO_L32P_1_P102") (pintype "bidirectional"))
      (node (ref "U3") (pin "27") (pinfunction "A11_27") (pintype "input"))
    )
    (net (code "94") (name "/XA12") (class "Default")
      (node (ref "U1") (pin "P101") (pinfunction "IO_L32N_1_P101") (pintype "bidirectional"))
      (node (ref "U3") (pin "28") (pinfunction "A12_28") (pintype "input"))
    )
    (net (code "95") (name "/XA13") (class "Default")
      (node (ref "U1") (pin "P100") (pinfunction "IO_L33P_1_P100") (pintype "bidirectional"))
      (node (ref "U3") (pin "29") (pinfunction "A13_29") (pintype "input"))
    )
    (net (code "96") (name "/XA14") (class "Default")
      (node (ref "U1") (pin "P111") (pinfunction "IO_L66N_SCP0_0_P111") (pintype "bidirectional"))
      (node (ref "U3") (pin "30") (pinfunction "A14_30") (pintype "input"))
    )
    (net (code "97") (name "/XA15") (class "Default")
      (node (ref "U1") (pin "P131") (pinfunction "IO_L35N_GCLK16_0_P131") (pintype "bidirectional"))
      (node (ref "U3") (pin "38") (pinfunction "A15_38") (pintype "input"))
    )
    (net (code "98") (name "/XA16") (class "Default")
      (node (ref "U1") (pin "P138") (pinfunction "IO_L4P_0_P138") (pintype "bidirectional"))
      (node (ref "U3") (pin "39") (pinfunction "A16_39") (pintype "input"))
    )
    (net (code "99") (name "/XA17") (class "Default")
      (node (ref "U1") (pin "P140") (pinfunction "IO_L3P_0_P140") (pintype "bidirectional"))
      (node (ref "U3") (pin "40") (pinfunction "A17_40") (pintype "input"))
    )
    (net (code "100") (name "/XA18") (class "Default")
      (node (ref "U1") (pin "P142") (pinfunction "IO_L2P_0_P142") (pintype "bidirectional"))
      (node (ref "U3") (pin "41") (pinfunction "A18/NC_41") (pintype "input"))
    )
    (net (code "101") (name "/XA19") (class "Default")
      (node (ref "U1") (pin "P105") (pinfunction "IO_L1P_1_P105") (pintype "bidirectional"))
      (node (ref "U3") (pin "25") (pinfunction "A19/NC_25") (pintype "input"))
    )
    (net (code "102") (name "/XA20") (class "Default")
      (node (ref "U1") (pin "P143") (pinfunction "IO_L1N_VREF_0_P143") (pintype "bidirectional"))
      (node (ref "U3") (pin "42") (pinfunction "A20/NC_42") (pintype "input"))
    )
    (net (code "103") (name "/XD0") (class "Default")
      (node (ref "U1") (pin "P132") (pinfunction "IO_L35P_GCLK17_0_P132") (pintype "bidirectional"))
      (node (ref "U3") (pin "9") (pinfunction "D0_9") (pintype "bidirectional"))
    )
    (net (code "104") (name "/XD1") (class "Default")
      (node (ref "U1") (pin "P127") (pinfunction "IO_L36P_GCLK15_0_P127") (pintype "bidirectional"))
      (node (ref "U3") (pin "10") (pinfunction "D1_10") (pintype "bidirectional"))
    )
    (net (code "105") (name "/XD2") (class "Default")
      (node (ref "U1") (pin "P124") (pinfunction "IO_L37P_GCLK13_0_P124") (pintype "bidirectional"))
      (node (ref "U3") (pin "13") (pinfunction "D2_13") (pintype "bidirectional"))
    )
    (net (code "106") (name "/XD3") (class "Default")
      (node (ref "U1") (pin "P123") (pinfunction "IO_L37N_GCLK12_0_P123") (pintype "bidirectional"))
      (node (ref "U3") (pin "14") (pinfunction "D3_14") (pintype "bidirectional"))
    )
    (net (code "107") (name "/XD4") (class "Default")
      (node (ref "U1") (pin "P115") (pinfunction "IO_L65P_SCP3_0_P115") (pintype "bidirectional"))
      (node (ref "U3") (pin "31") (pinfunction "D4_31") (pintype "bidirectional"))
    )
    (net (code "108") (name "/XD5") (class "Default")
      (node (ref "U1") (pin "P117") (pinfunction "IO_L64P_SCP5_0_P117") (pintype "bidirectional"))
      (node (ref "U3") (pin "32") (pinfunction "D5_32") (pintype "bidirectional"))
    )
    (net (code "109") (name "/XD6") (class "Default")
      (node (ref "U1") (pin "P119") (pinfunction "IO_L63P_SCP7_0_P119") (pintype "bidirectional"))
      (node (ref "U3") (pin "35") (pinfunction "D6_35") (pintype "bidirectional"))
    )
    (net (code "110") (name "/XD7") (class "Default")
      (node (ref "U1") (pin "P126") (pinfunction "IO_L36N_GCLK14_0_P126") (pintype "bidirectional"))
      (node (ref "U3") (pin "36") (pinfunction "D7_36") (pintype "bidirectional"))
    )
    (net (code "111") (name "1.2V") (class "Default")
      (node (ref "C10") (pin "2") (pinfunction "2_2") (pintype "passive"))
      (node (ref "C11") (pin "2") (pinfunction "2_2") (pintype "passive"))
      (node (ref "C12") (pin "2") (pinfunction "2_2") (pintype "passive"))
      (node (ref "C13") (pin "2") (pinfunction "2_2") (pintype "passive"))
      (node (ref "C9") (pin "2") (pinfunction "2_2") (pintype "passive"))
      (node (ref "L2") (pin "2") (pinfunction "2_2") (pintype "passive"))
      (node (ref "U1") (pin "P128") (pinfunction "VCCINT_P128") (pintype "input"))
      (node (ref "U1") (pin "P19") (pinfunction "VCCINT_P19") (pintype "input"))
      (node (ref "U1") (pin "P28") (pinfunction "VCCINT_P28") (pintype "input"))
      (node (ref "U1") (pin "P52") (pinfunction "VCCINT_P52") (pintype "input"))
      (node (ref "U1") (pin "P89") (pinfunction "VCCINT_P89") (pintype "input"))
    )
    (net (code "112") (name "3.3V") (class "Default")
      (node (ref "C14") (pin "2") (pinfunction "2_2") (pintype "passive"))
      (node (ref "C15") (pin "2") (pinfunction "2_2") (pintype "passive"))
      (node (ref "C16") (pin "2") (pinfunction "2_2") (pintype "passive"))
      (node (ref "C17") (pin "2") (pinfunction "2_2") (pintype "passive"))
      (node (ref "C18") (pin "2") (pinfunction "2_2") (pintype "passive"))
      (node (ref "C19") (pin "2") (pinfunction "2_2") (pintype "passive"))
      (node (ref "C20") (pin "2") (pinfunction "2_2") (pintype "passive"))
      (node (ref "C21") (pin "2") (pinfunction "2_2") (pintype "passive"))
      (node (ref "C22") (pin "2") (pinfunction "2_2") (pintype "passive"))
      (node (ref "C23") (pin "2") (pinfunction "2_2") (pintype "passive"))
      (node (ref "C24") (pin "2") (pinfunction "2_2") (pintype "passive"))
      (node (ref "C25") (pin "2") (pinfunction "2_2") (pintype "passive"))
      (node (ref "C26") (pin "1") (pinfunction "1_1") (pintype "passive"))
      (node (ref "C27") (pin "2") (pinfunction "2_2") (pintype "passive"))
      (node (ref "J11") (pin "1") (pinfunction "1_1") (pintype "passive"))
      (node (ref "J12") (pin "12") (pinfunction "12_12") (pintype "passive"))
      (node (ref "JTAG") (pin "1") (pinfunction "S_1") (pintype "passive"))
      (node (ref "L1") (pin "2") (pinfunction "2_2") (pintype "passive"))
      (node (ref "R24") (pin "2") (pinfunction "2_2") (pintype "passive"))
      (node (ref "R27") (pin "2") (pinfunction "2_2") (pintype "passive"))
      (node (ref "R30") (pin "1") (pinfunction "1_1") (pintype "passive"))
      (node (ref "R31") (pin "2") (pinfunction "2_2") (pintype "passive"))
      (node (ref "R32") (pin "2") (pinfunction "2_2") (pintype "passive"))
      (node (ref "RGB") (pin "4") (pinfunction "S_4") (pintype "passive"))
      (node (ref "SDCARD") (pin "4") (pinfunction "VDD_4") (pintype "power_in"))
      (node (ref "U1") (pin "P103") (pinfunction "VCCO_1_P103") (pintype "input"))
      (node (ref "U1") (pin "P122") (pinfunction "VCCO_0_P122") (pintype "input"))
      (node (ref "U1") (pin "P125") (pinfunction "VCCO_0_P125") (pintype "input"))
      (node (ref "U1") (pin "P129") (pinfunction "VCCAUX_P129") (pintype "input"))
      (node (ref "U1") (pin "P135") (pinfunction "VCCO_0_P135") (pintype "input"))
      (node (ref "U1") (pin "P18") (pinfunction "VCCO_3_P18") (pintype "input"))
      (node (ref "U1") (pin "P20") (pinfunction "VCCAUX_P20") (pintype "input"))
      (node (ref "U1") (pin "P31") (pinfunction "VCCO_3_P31") (pintype "input"))
      (node (ref "U1") (pin "P36") (pinfunction "VCCAUX_P36") (pintype "input"))
      (node (ref "U1") (pin "P4") (pinfunction "VCCO_3_P4") (pintype "input"))
      (node (ref "U1") (pin "P42") (pinfunction "VCCO_2_P42") (pintype "input"))
      (node (ref "U1") (pin "P53") (pinfunction "VCCAUX_P53") (pintype "input"))
      (node (ref "U1") (pin "P63") (pinfunction "VCCO_2_P63") (pintype "input"))
      (node (ref "U1") (pin "P69") (pinfunction "IO_L1N_M0_CMPMISO_2_P69") (pintype "bidirectional"))
      (node (ref "U1") (pin "P76") (pinfunction "VCCO_1_P76") (pintype "input"))
      (node (ref "U1") (pin "P86") (pinfunction "VCCO_1_P86") (pintype "input"))
      (node (ref "U1") (pin "P90") (pinfunction "VCCAUX_P90") (pintype "input"))
      (node (ref "U2") (pin "8") (pinfunction "VCC_8") (pintype "bidirectional"))
      (node (ref "U3") (pin "11") (pinfunction "VDD_11") (pintype "input"))
      (node (ref "U3") (pin "33") (pinfunction "VDD_33") (pintype "input"))
      (node (ref "U5") (pin "4") (pinfunction "VCC_4") (pintype "power_in"))
    )
    (net (code "113") (name "5V") (class "Default")
      (node (ref "C28") (pin "1") (pinfunction "1_1") (pintype "passive"))
      (node (ref "C30") (pin "1") (pinfunction "1_1") (pintype "passive"))
      (node (ref "C32") (pin "2") (pinfunction "2_2") (pintype "passive"))
      (node (ref "C33") (pin "2") (pinfunction "2_2") (pintype "passive"))
      (node (ref "J12") (pin "1") (pinfunction "1_1") (pintype "passive"))
      (node (ref "L3") (pin "2") (pinfunction "2_2") (pintype "passive"))
      (node (ref "PS/2") (pin "4") (pinfunction "4_4") (pintype "passive"))
      (node (ref "R5") (pin "1") (pinfunction "1_1") (pintype "passive"))
      (node (ref "R7") (pin "2") (pinfunction "2_2") (pintype "passive"))
      (node (ref "U4") (pin "14") (pinfunction "DPOS_14") (pintype "bidirectional"))
      (node (ref "U4") (pin "15") (pinfunction "VSYNC_15") (pintype "bidirectional"))
      (node (ref "U4") (pin "4") (pinfunction "APOS_4") (pintype "bidirectional"))
      (node (ref "U4") (pin "5") (pinfunction "CE_5") (pintype "bidirectional"))
      (node (ref "U6") (pin "3") (pinfunction "VIN_3") (pintype "input"))
      (node (ref "U7") (pin "3") (pinfunction "VIN_3") (pintype "input"))
    )
    (net (code "114") (name "GND") (class "Default")
      (node (ref "AUDIO") (pin "SLEEVE") (pinfunction "SLEEVE_SLEEVE") (pintype "bidirectional"))
      (node (ref "C1") (pin "2") (pinfunction "2_2") (pintype "passive"))
      (node (ref "C10") (pin "1") (pinfunction "1_1") (pintype "passive"))
      (node (ref "C11") (pin "1") (pinfunction "1_1") (pintype "passive"))
      (node (ref "C12") (pin "1") (pinfunction "1_1") (pintype "passive"))
      (node (ref "C13") (pin "1") (pinfunction "1_1") (pintype "passive"))
      (node (ref "C14") (pin "1") (pinfunction "1_1") (pintype "passive"))
      (node (ref "C15") (pin "1") (pinfunction "1_1") (pintype "passive"))
      (node (ref "C16") (pin "1") (pinfunction "1_1") (pintype "passive"))
      (node (ref "C17") (pin "1") (pinfunction "1_1") (pintype "passive"))
      (node (ref "C18") (pin "1") (pinfunction "1_1") (pintype "passive"))
      (node (ref "C19") (pin "1") (pinfunction "1_1") (pintype "passive"))
      (node (ref "C2") (pin "2") (pinfunction "2_2") (pintype "passive"))
      (node (ref "C20") (pin "1") (pinfunction "1_1") (pintype "passive"))
      (node (ref "C21") (pin "1") (pinfunction "1_1") (pintype "passive"))
      (node (ref "C22") (pin "1") (pinfunction "1_1") (pintype "passive"))
      (node (ref "C23") (pin "1") (pinfunction "1_1") (pintype "passive"))
      (node (ref "C24") (pin "1") (pinfunction "1_1") (pintype "passive"))
      (node (ref "C25") (pin "1") (pinfunction "1_1") (pintype "passive"))
      (node (ref "C26") (pin "2") (pinfunction "2_2") (pintype "passive"))
      (node (ref "C27") (pin "1") (pinfunction "1_1") (pintype "passive"))
      (node (ref "C28") (pin "2") (pinfunction "2_2") (pintype "passive"))
      (node (ref "C29") (pin "2") (pinfunction "2_2") (pintype "passive"))
      (node (ref "C3") (pin "2") (pinfunction "2_2") (pintype "passive"))
      (node (ref "C30") (pin "2") (pinfunction "2_2") (pintype "passive"))
      (node (ref "C31") (pin "2") (pinfunction "2_2") (pintype "passive"))
      (node (ref "C32") (pin "1") (pinfunction "1_1") (pintype "passive"))
      (node (ref "C33") (pin "1") (pinfunction "1_1") (pintype "passive"))
      (node (ref "C4") (pin "2") (pinfunction "2_2") (pintype "passive"))
      (node (ref "C9") (pin "1") (pinfunction "1_1") (pintype "passive"))
      (node (ref "CVBS") (pin "4") (pinfunction "2_4") (pintype "passive"))
      (node (ref "D1") (pin "A") (pinfunction "A_A") (pintype "passive"))
      (node (ref "D2") (pin "K") (pinfunction "C_K") (pintype "passive"))
      (node (ref "D3") (pin "K") (pinfunction "C_K") (pintype "passive"))
      (node (ref "D4") (pin "C") (pinfunction "C_C") (pintype "passive"))
      (node (ref "D5") (pin "C") (pinfunction "C_C") (pintype "passive"))
      (node (ref "EAR") (pin "SLEEVE") (pinfunction "SLEEVE_SLEEVE") (pintype "bidirectional"))
      (node (ref "J10") (pin "12") (pinfunction "12_12") (pintype "passive"))
      (node (ref "J11") (pin "12") (pinfunction "12_12") (pintype "passive"))
      (node (ref "JOYSTICK") (pin "8") (pinfunction "8_8") (pintype "passive"))
      (node (ref "JTAG") (pin "6") (pinfunction "S_6") (pintype "passive"))
      (node (ref "PROG") (pin "1") (pinfunction "1_1") (pintype "passive"))
      (node (ref "PS/2") (pin "3") (pinfunction "3_3") (pintype "passive"))
      (node (ref "PWCON") (pin "1") (pinfunction "1_1") (pintype "passive"))
      (node (ref "PWUSB") (pin "5") (pinfunction "GND_5") (pintype "bidirectional"))
      (node (ref "R1") (pin "2") (pinfunction "2_2") (pintype "passive"))
      (node (ref "R2") (pin "2") (pinfunction "2_2") (pintype "passive"))
      (node (ref "R29") (pin "2") (pinfunction "2_2") (pintype "passive"))
      (node (ref "R3") (pin "2") (pinfunction "2_2") (pintype "passive"))
      (node (ref "RGB") (pin "1") (pinfunction "S_1") (pintype "passive"))
      (node (ref "SDCARD") (pin "3") (pinfunction "VSS1_3") (pintype "power_in"))
      (node (ref "SDCARD") (pin "6") (pinfunction "VSS2_6") (pintype "power_in"))
      (node (ref "SDCARD") (pin "M1") (pinfunction "GND_M1") (pintype "power_in"))
      (node (ref "SDCARD") (pin "M2") (pinfunction "GND_M2") (pintype "power_in"))
      (node (ref "SDCARD") (pin "M3") (pinfunction "GND_M3") (pintype "power_in"))
      (node (ref "SDCARD") (pin "M4") (pinfunction "GND_M4") (pintype "power_in"))
      (node (ref "T1") (pin "2") (pinfunction "E_2") (pintype "passive"))
      (node (ref "U1") (pin "P108") (pinfunction "GND_P108") (pintype "power_in"))
      (node (ref "U1") (pin "P113") (pinfunction "GND_P113") (pintype "power_in"))
      (node (ref "U1") (pin "P13") (pinfunction "GND_P13") (pintype "power_in"))
      (node (ref "U1") (pin "P130") (pinfunction "GND_P130") (pintype "power_in"))
      (node (ref "U1") (pin "P136") (pinfunction "GND_P136") (pintype "power_in"))
      (node (ref "U1") (pin "P144") (pinfunction "IO_L1P_HSWAPEN_0_P144") (pintype "bidirectional"))
      (node (ref "U1") (pin "P25") (pinfunction "GND_P25") (pintype "power_in"))
      (node (ref "U1") (pin "P3") (pinfunction "GND_P3") (pintype "power_in"))
      (node (ref "U1") (pin "P49") (pinfunction "GND_P49") (pintype "power_in"))
      (node (ref "U1") (pin "P54") (pinfunction "GND_P54") (pintype "power_in"))
      (node (ref "U1") (pin "P60") (pinfunction "IO_L13P_M1_2_P60") (pintype "bidirectional"))
      (node (ref "U1") (pin "P68") (pinfunction "GND_P68") (pintype "power_in"))
      (node (ref "U1") (pin "P73") (pinfunction "SUSPEND_P73") (pintype "input"))
      (node (ref "U1") (pin "P77") (pinfunction "GND_P77") (pintype "power_in"))
      (node (ref "U1") (pin "P91") (pinfunction "GND_P91") (pintype "power_in"))
      (node (ref "U1") (pin "P96") (pinfunction "GND_P96") (pintype "power_in"))
      (node (ref "U2") (pin "4") (pinfunction "GND_4") (pintype "bidirectional"))
      (node (ref "U3") (pin "12") (pinfunction "VSS_12") (pintype "input"))
      (node (ref "U3") (pin "34") (pinfunction "VSS_34") (pintype "input"))
      (node (ref "U3") (pin "37") (pinfunction "~{OE}_37") (pintype "input"))
      (node (ref "U3") (pin "8") (pinfunction "~{CS}_8") (pintype "input"))
      (node (ref "U4") (pin "12") (pinfunction "YTRAP_12") (pintype "bidirectional"))
      (node (ref "U4") (pin "13") (pinfunction "DGND_13") (pintype "bidirectional"))
      (node (ref "U4") (pin "2") (pinfunction "AGND_2") (pintype "bidirectional"))
      (node (ref "U5") (pin "2") (pinfunction "GND_2") (pintype "power_in"))
      (node (ref "U6") (pin "1") (pinfunction "GND_1") (pintype "power_in"))
      (node (ref "U7") (pin "1") (pinfunction "GND_1") (pintype "power_in"))
    )
    (net (code "115") (name "Net-(C3-Pad1)") (class "Default")
      (node (ref "C3") (pin "1") (pinfunction "1_1") (pintype "passive"))
      (node (ref "C35") (pin "1") (pinfunction "1_1") (pintype "passive"))
      (node (ref "R23") (pin "1") (pinfunction "1_1") (pintype "passive"))
    )
    (net (code "116") (name "Net-(C5-Pad2)") (class "Default")
      (node (ref "C5") (pin "2") (pinfunction "2_2") (pintype "passive"))
      (node (ref "R15") (pin "2") (pinfunction "2_2") (pintype "passive"))
    )
    (net (code "117") (name "Net-(C34-Pad1)") (class "Default")
      (node (ref "C34") (pin "1") (pinfunction "1_1") (pintype "passive"))
      (node (ref "C4") (pin "1") (pinfunction "1_1") (pintype "passive"))
      (node (ref "R22") (pin "1") (pinfunction "1_1") (pintype "passive"))
    )
    (net (code "118") (name "Net-(C36-Pad-)") (class "Default")
      (node (ref "C36") (pin "-") (pinfunction "-_-") (pintype "passive"))
      (node (ref "R4") (pin "1") (pinfunction "1_1") (pintype "passive"))
    )
    (net (code "119") (name "Net-(CVBS-1)") (class "Default")
      (node (ref "CVBS") (pin "3") (pinfunction "1_3") (pintype "passive"))
      (node (ref "R4") (pin "2") (pinfunction "2_2") (pintype "passive"))
    )
    (net (code "120") (name "Net-(D1-C)") (class "Default")
      (node (ref "C2") (pin "1") (pinfunction "1_1") (pintype "passive"))
      (node (ref "C5") (pin "1") (pinfunction "1_1") (pintype "passive"))
      (node (ref "D1") (pin "K") (pinfunction "C_K") (pintype "passive"))
      (node (ref "R28") (pin "1") (pinfunction "1_1") (pintype "passive"))
    )
    (net (code "121") (name "Net-(D2-PadA)") (class "Default")
      (node (ref "D2") (pin "A") (pinfunction "A_A") (pintype "passive"))
      (node (ref "R25") (pin "2") (pinfunction "2_2") (pintype "passive"))
      (node (ref "Y1") (pin "1") (pinfunction "1_1") (pintype "passive"))
    )
    (net (code "122") (name "Net-(D3-PadA)") (class "Default")
      (node (ref "D3") (pin "A") (pinfunction "A_A") (pintype "passive"))
      (node (ref "R26") (pin "1") (pinfunction "1_1") (pintype "passive"))
      (node (ref "Y2") (pin "1") (pinfunction "1_1") (pintype "passive"))
    )
    (net (code "123") (name "Net-(D4-PadA)") (class "Default")
      (node (ref "D4") (pin "A") (pinfunction "A_A") (pintype "passive"))
      (node (ref "R6") (pin "1") (pinfunction "1_1") (pintype "passive"))
    )
    (net (code "124") (name "Net-(D5-PadA)") (class "Default")
      (node (ref "D5") (pin "A") (pinfunction "A_A") (pintype "passive"))
      (node (ref "R7") (pin "1") (pinfunction "1_1") (pintype "passive"))
    )
    (net (code "125") (name "Net-(EAR-LEFT)") (class "Default")
      (node (ref "EAR") (pin "TIP") (pinfunction "LEFT_TIP") (pintype "bidirectional"))
      (node (ref "R15") (pin "1") (pinfunction "1_1") (pintype "passive"))
      (node (ref "R29") (pin "1") (pinfunction "1_1") (pintype "passive"))
    )
    (net (code "126") (name "Net-(J16-Pad4)") (class "Default")
      (node (ref "J16") (pin "4") (pinfunction "4_4") (pintype "passive"))
      (node (ref "R5") (pin "2") (pinfunction "2_2") (pintype "passive"))
    )
    (net (code "127") (name "Net-(L3-Pad1)") (class "Default")
      (node (ref "L3") (pin "1") (pinfunction "1_1") (pintype "passive"))
      (node (ref "SW") (pin "1") (pinfunction "1_1") (pintype "passive"))
    )
    (net (code "128") (name "Net-(PS/2-Pad1)") (class "Default")
      (node (ref "PS/2") (pin "1") (pinfunction "1_1") (pintype "passive"))
      (node (ref "R8") (pin "1") (pinfunction "1_1") (pintype "passive"))
    )
    (net (code "129") (name "Net-(PS/2-Pad2)") (class "Default")
      (node (ref "PS/2") (pin "2") (pinfunction "2_2") (pintype "passive"))
      (node (ref "R9") (pin "1") (pinfunction "1_1") (pintype "passive"))
    )
    (net (code "130") (name "Net-(PS/2-Pad5)") (class "Default")
      (node (ref "PS/2") (pin "5") (pinfunction "5_5") (pintype "passive"))
      (node (ref "R10") (pin "1") (pinfunction "1_1") (pintype "passive"))
    )
    (net (code "131") (name "Net-(PS/2-Pad6)") (class "Default")
      (node (ref "PS/2") (pin "6") (pinfunction "6_6") (pintype "passive"))
      (node (ref "R11") (pin "1") (pinfunction "1_1") (pintype "passive"))
    )
    (net (code "132") (name "Net-(PWUSB-VCC)") (class "Default")
      (node (ref "PWCON") (pin "2") (pinfunction "2_2") (pintype "passive"))
      (node (ref "PWUSB") (pin "1") (pinfunction "VCC_1") (pintype "bidirectional"))
      (node (ref "SW") (pin "2") (pinfunction "2_2") (pintype "passive"))
    )
    (net (code "133") (name "Net-(SDCARD-DAT1)") (class "Default")
      (node (ref "R31") (pin "1") (pinfunction "1_1") (pintype "passive"))
      (node (ref "SDCARD") (pin "8") (pinfunction "DAT1_8") (pintype "bidirectional"))
    )
    (net (code "134") (name "Net-(SDCARD-DAT2)") (class "Default")
      (node (ref "R32") (pin "1") (pinfunction "1_1") (pintype "passive"))
      (node (ref "SDCARD") (pin "9") (pinfunction "DAT2_9") (pintype "bidirectional"))
    )
    (net (code "135") (name "Net-(T1-B)") (class "Default")
      (node (ref "R28") (pin "2") (pinfunction "2_2") (pintype "passive"))
      (node (ref "T1") (pin "1") (pinfunction "B_1") (pintype "passive"))
    )
    (net (code "136") (name "Net-(U1C-PROGRAM_B_2)") (class "Default")
      (node (ref "PROG") (pin "2") (pinfunction "2_2") (pintype "passive"))
      (node (ref "R24") (pin "1") (pinfunction "1_1") (pintype "passive"))
      (node (ref "U1") (pin "P37") (pinfunction "PROGRAM_B_2_P37") (pintype "input"))
    )
    (net (code "137") (name "Net-(U4-4FSC)") (class "Default")
      (node (ref "C1") (pin "1") (pinfunction "1_1") (pintype "passive"))
      (node (ref "U4") (pin "3") (pinfunction "4FSC_3") (pintype "bidirectional"))
      (node (ref "Y1") (pin "2") (pinfunction "2_2") (pintype "passive"))
      (node (ref "Y2") (pin "2") (pinfunction "2_2") (pintype "passive"))
    )
    (net (code "138") (name "Net-(U4-BIN)") (class "Default")
      (node (ref "C8") (pin "1") (pinfunction "1_1") (pintype "passive"))
      (node (ref "U4") (pin "8") (pinfunction "BIN_8") (pintype "bidirectional"))
    )
    (net (code "139") (name "Net-(U4-COMP)") (class "Default")
      (node (ref "C36") (pin "+") (pinfunction "+_+") (pintype "passive"))
      (node (ref "U4") (pin "10") (pinfunction "COMP_10") (pintype "bidirectional"))
    )
    (net (code "140") (name "Net-(U4-GIN)") (class "Default")
      (node (ref "C7") (pin "1") (pinfunction "1_1") (pintype "passive"))
      (node (ref "U4") (pin "7") (pinfunction "GIN_7") (pintype "bidirectional"))
    )
    (net (code "141") (name "Net-(U4-RIN)") (class "Default")
      (node (ref "C6") (pin "1") (pinfunction "1_1") (pintype "passive"))
      (node (ref "U4") (pin "6") (pinfunction "RIN_6") (pintype "bidirectional"))
    )
    (net (code "142") (name "Net-(U6-VOUT)") (class "Default")
      (node (ref "C29") (pin "1") (pinfunction "1_1") (pintype "passive"))
      (node (ref "L1") (pin "1") (pinfunction "1_1") (pintype "passive"))
      (node (ref "U6") (pin "2") (pinfunction "VOUT_2") (pintype "output"))
    )
    (net (code "143") (name "Net-(U7-VOUT)") (class "Default")
      (node (ref "C31") (pin "1") (pinfunction "1_1") (pintype "passive"))
      (node (ref "L2") (pin "1") (pinfunction "1_1") (pintype "passive"))
      (node (ref "U7") (pin "2") (pinfunction "VOUT_2") (pintype "output"))
    )
    (net (code "144") (name "unconnected-(EAR-RIGHT-PadRING)") (class "Default")
      (node (ref "EAR") (pin "RING") (pinfunction "RIGHT_RING") (pintype "bidirectional"))
    )
    (net (code "145") (name "unconnected-(J10-Pad11)") (class "Default")
      (node (ref "J10") (pin "11") (pinfunction "11_11") (pintype "passive"))
    )
    (net (code "146") (name "unconnected-(PWUSB-D+-Pad3)") (class "Default")
      (node (ref "PWUSB") (pin "3") (pinfunction "D+_3") (pintype "bidirectional"))
    )
    (net (code "147") (name "unconnected-(PWUSB-D--Pad2)") (class "Default")
      (node (ref "PWUSB") (pin "2") (pinfunction "D-_2") (pintype "bidirectional"))
    )
    (net (code "148") (name "unconnected-(PWUSB-ID-Pad4)") (class "Default")
      (node (ref "PWUSB") (pin "4") (pinfunction "ID_4") (pintype "bidirectional"))
    )
    (net (code "149") (name "unconnected-(PWUSB-SHIELD-Pad6)") (class "Default")
      (node (ref "PWUSB") (pin "6") (pinfunction "SHIELD_6") (pintype "bidirectional"))
    )
    (net (code "150") (name "unconnected-(SDCARD-CDI#-Pad10)") (class "Default")
      (node (ref "SDCARD") (pin "10") (pinfunction "CDI#_10") (pintype "output"))
    )
    (net (code "151") (name "unconnected-(SDCARD-WP-Pad11)") (class "Default")
      (node (ref "SDCARD") (pin "11") (pinfunction "WP_11") (pintype "output"))
    )
    (net (code "152") (name "unconnected-(U1C-CMPCS_B_2-PadP72)") (class "Default")
      (node (ref "U1") (pin "P72") (pinfunction "CMPCS_B_2_P72") (pintype "bidirectional"))
    )
    (net (code "153") (name "unconnected-(U1C-DONE_2-PadP71)") (class "Default")
      (node (ref "U1") (pin "P71") (pinfunction "DONE_2_P71") (pintype "bidirectional"))
    )
    (net (code "154") (name "unconnected-(U4-CRMA-Pad9)") (class "Default")
      (node (ref "U4") (pin "9") (pinfunction "CRMA_9") (pintype "bidirectional"))
    )
    (net (code "155") (name "unconnected-(U4-LUMA-Pad11)") (class "Default")
      (node (ref "U4") (pin "11") (pinfunction "LUMA_11") (pintype "bidirectional"))
    )
    (net (code "156") (name "unconnected-(U5-E{slash}D-Pad1)") (class "Default")
      (node (ref "U5") (pin "1") (pinfunction "E/D_1") (pintype "input"))
    )
  )
)
